# pmod_debug.net
KiCad netlist of a schematic drawn in EAGLE
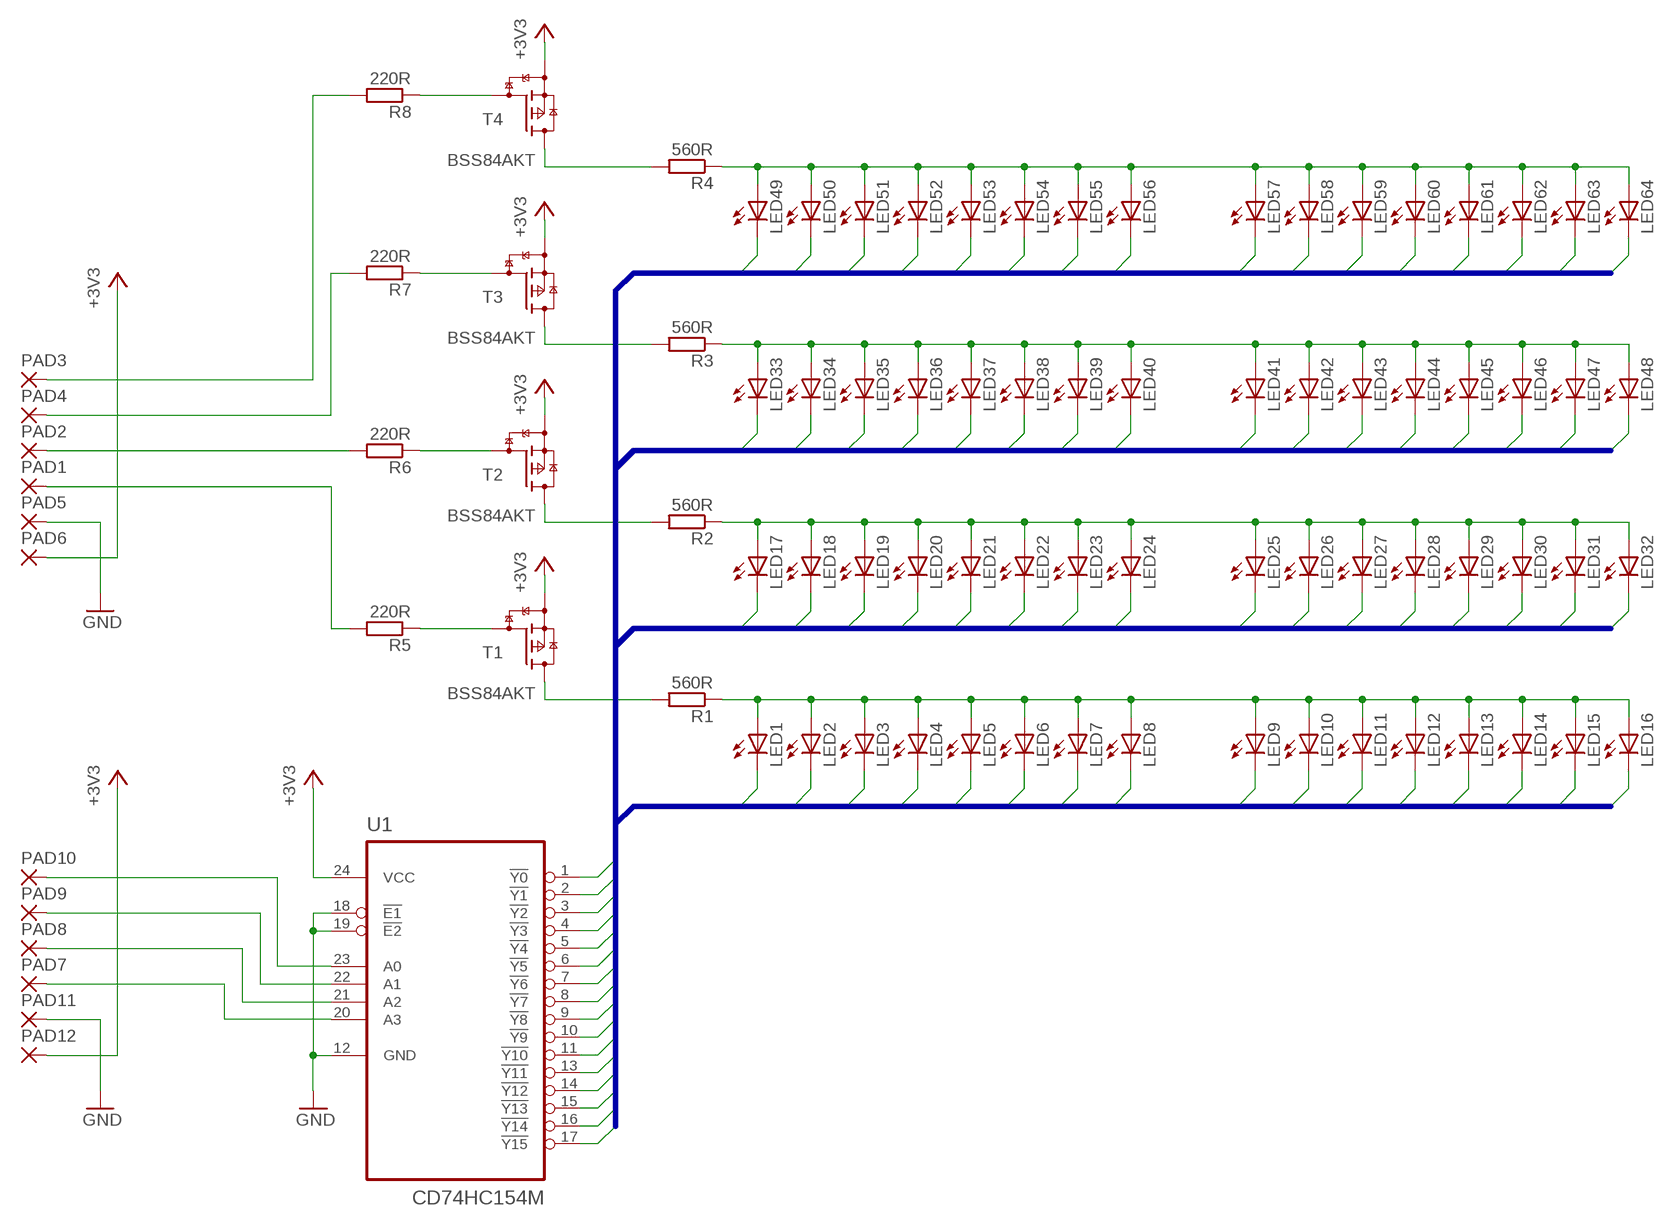
[diagram p0: schematic, sheet 1]

(export (version "E")
  (design (tool "Eeschema 10.0.6"))
  (components
    (comp (ref "LED1")
      (value "LEDCHIP-LED0603")
      (footprint "eagle-import:CHIP-LED0603")
      (libsource (lib "eagle-import") (part "LEDCHIP-LED0603"))
    )
    (comp (ref "LED2")
      (value "LEDCHIP-LED0603")
      (footprint "eagle-import:CHIP-LED0603")
      (libsource (lib "eagle-import") (part "LEDCHIP-LED0603"))
    )
    (comp (ref "LED3")
      (value "LEDCHIP-LED0603")
      (footprint "eagle-import:CHIP-LED0603")
      (libsource (lib "eagle-import") (part "LEDCHIP-LED0603"))
    )
    (comp (ref "LED4")
      (value "LEDCHIP-LED0603")
      (footprint "eagle-import:CHIP-LED0603")
      (libsource (lib "eagle-import") (part "LEDCHIP-LED0603"))
    )
    (comp (ref "LED5")
      (value "LEDCHIP-LED0603")
      (footprint "eagle-import:CHIP-LED0603")
      (libsource (lib "eagle-import") (part "LEDCHIP-LED0603"))
    )
    (comp (ref "LED6")
      (value "LEDCHIP-LED0603")
      (footprint "eagle-import:CHIP-LED0603")
      (libsource (lib "eagle-import") (part "LEDCHIP-LED0603"))
    )
    (comp (ref "LED7")
      (value "LEDCHIP-LED0603")
      (footprint "eagle-import:CHIP-LED0603")
      (libsource (lib "eagle-import") (part "LEDCHIP-LED0603"))
    )
    (comp (ref "LED8")
      (value "LEDCHIP-LED0603")
      (footprint "eagle-import:CHIP-LED0603")
      (libsource (lib "eagle-import") (part "LEDCHIP-LED0603"))
    )
    (comp (ref "LED9")
      (value "LEDCHIP-LED0603")
      (footprint "eagle-import:CHIP-LED0603")
      (libsource (lib "eagle-import") (part "LEDCHIP-LED0603"))
    )
    (comp (ref "LED10")
      (value "LEDCHIP-LED0603")
      (footprint "eagle-import:CHIP-LED0603")
      (libsource (lib "eagle-import") (part "LEDCHIP-LED0603"))
    )
    (comp (ref "LED11")
      (value "LEDCHIP-LED0603")
      (footprint "eagle-import:CHIP-LED0603")
      (libsource (lib "eagle-import") (part "LEDCHIP-LED0603"))
    )
    (comp (ref "LED12")
      (value "LEDCHIP-LED0603")
      (footprint "eagle-import:CHIP-LED0603")
      (libsource (lib "eagle-import") (part "LEDCHIP-LED0603"))
    )
    (comp (ref "LED13")
      (value "LEDCHIP-LED0603")
      (footprint "eagle-import:CHIP-LED0603")
      (libsource (lib "eagle-import") (part "LEDCHIP-LED0603"))
    )
    (comp (ref "LED14")
      (value "LEDCHIP-LED0603")
      (footprint "eagle-import:CHIP-LED0603")
      (libsource (lib "eagle-import") (part "LEDCHIP-LED0603"))
    )
    (comp (ref "LED15")
      (value "LEDCHIP-LED0603")
      (footprint "eagle-import:CHIP-LED0603")
      (libsource (lib "eagle-import") (part "LEDCHIP-LED0603"))
    )
    (comp (ref "LED16")
      (value "LEDCHIP-LED0603")
      (footprint "eagle-import:CHIP-LED0603")
      (libsource (lib "eagle-import") (part "LEDCHIP-LED0603"))
    )
    (comp (ref "LED17")
      (value "LEDCHIP-LED0603")
      (footprint "eagle-import:CHIP-LED0603")
      (libsource (lib "eagle-import") (part "LEDCHIP-LED0603"))
    )
    (comp (ref "LED18")
      (value "LEDCHIP-LED0603")
      (footprint "eagle-import:CHIP-LED0603")
      (libsource (lib "eagle-import") (part "LEDCHIP-LED0603"))
    )
    (comp (ref "LED19")
      (value "LEDCHIP-LED0603")
      (footprint "eagle-import:CHIP-LED0603")
      (libsource (lib "eagle-import") (part "LEDCHIP-LED0603"))
    )
    (comp (ref "LED20")
      (value "LEDCHIP-LED0603")
      (footprint "eagle-import:CHIP-LED0603")
      (libsource (lib "eagle-import") (part "LEDCHIP-LED0603"))
    )
    (comp (ref "LED21")
      (value "LEDCHIP-LED0603")
      (footprint "eagle-import:CHIP-LED0603")
      (libsource (lib "eagle-import") (part "LEDCHIP-LED0603"))
    )
    (comp (ref "LED22")
      (value "LEDCHIP-LED0603")
      (footprint "eagle-import:CHIP-LED0603")
      (libsource (lib "eagle-import") (part "LEDCHIP-LED0603"))
    )
    (comp (ref "LED23")
      (value "LEDCHIP-LED0603")
      (footprint "eagle-import:CHIP-LED0603")
      (libsource (lib "eagle-import") (part "LEDCHIP-LED0603"))
    )
    (comp (ref "LED24")
      (value "LEDCHIP-LED0603")
      (footprint "eagle-import:CHIP-LED0603")
      (libsource (lib "eagle-import") (part "LEDCHIP-LED0603"))
    )
    (comp (ref "LED25")
      (value "LEDCHIP-LED0603")
      (footprint "eagle-import:CHIP-LED0603")
      (libsource (lib "eagle-import") (part "LEDCHIP-LED0603"))
    )
    (comp (ref "LED26")
      (value "LEDCHIP-LED0603")
      (footprint "eagle-import:CHIP-LED0603")
      (libsource (lib "eagle-import") (part "LEDCHIP-LED0603"))
    )
    (comp (ref "LED27")
      (value "LEDCHIP-LED0603")
      (footprint "eagle-import:CHIP-LED0603")
      (libsource (lib "eagle-import") (part "LEDCHIP-LED0603"))
    )
    (comp (ref "LED28")
      (value "LEDCHIP-LED0603")
      (footprint "eagle-import:CHIP-LED0603")
      (libsource (lib "eagle-import") (part "LEDCHIP-LED0603"))
    )
    (comp (ref "LED29")
      (value "LEDCHIP-LED0603")
      (footprint "eagle-import:CHIP-LED0603")
      (libsource (lib "eagle-import") (part "LEDCHIP-LED0603"))
    )
    (comp (ref "LED30")
      (value "LEDCHIP-LED0603")
      (footprint "eagle-import:CHIP-LED0603")
      (libsource (lib "eagle-import") (part "LEDCHIP-LED0603"))
    )
    (comp (ref "LED31")
      (value "LEDCHIP-LED0603")
      (footprint "eagle-import:CHIP-LED0603")
      (libsource (lib "eagle-import") (part "LEDCHIP-LED0603"))
    )
    (comp (ref "LED32")
      (value "LEDCHIP-LED0603")
      (footprint "eagle-import:CHIP-LED0603")
      (libsource (lib "eagle-import") (part "LEDCHIP-LED0603"))
    )
    (comp (ref "LED33")
      (value "LEDCHIP-LED0603")
      (footprint "eagle-import:CHIP-LED0603")
      (libsource (lib "eagle-import") (part "LEDCHIP-LED0603"))
    )
    (comp (ref "LED34")
      (value "LEDCHIP-LED0603")
      (footprint "eagle-import:CHIP-LED0603")
      (libsource (lib "eagle-import") (part "LEDCHIP-LED0603"))
    )
    (comp (ref "LED35")
      (value "LEDCHIP-LED0603")
      (footprint "eagle-import:CHIP-LED0603")
      (libsource (lib "eagle-import") (part "LEDCHIP-LED0603"))
    )
    (comp (ref "LED36")
      (value "LEDCHIP-LED0603")
      (footprint "eagle-import:CHIP-LED0603")
      (libsource (lib "eagle-import") (part "LEDCHIP-LED0603"))
    )
    (comp (ref "LED37")
      (value "LEDCHIP-LED0603")
      (footprint "eagle-import:CHIP-LED0603")
      (libsource (lib "eagle-import") (part "LEDCHIP-LED0603"))
    )
    (comp (ref "LED38")
      (value "LEDCHIP-LED0603")
      (footprint "eagle-import:CHIP-LED0603")
      (libsource (lib "eagle-import") (part "LEDCHIP-LED0603"))
    )
    (comp (ref "LED39")
      (value "LEDCHIP-LED0603")
      (footprint "eagle-import:CHIP-LED0603")
      (libsource (lib "eagle-import") (part "LEDCHIP-LED0603"))
    )
    (comp (ref "LED40")
      (value "LEDCHIP-LED0603")
      (footprint "eagle-import:CHIP-LED0603")
      (libsource (lib "eagle-import") (part "LEDCHIP-LED0603"))
    )
    (comp (ref "LED41")
      (value "LEDCHIP-LED0603")
      (footprint "eagle-import:CHIP-LED0603")
      (libsource (lib "eagle-import") (part "LEDCHIP-LED0603"))
    )
    (comp (ref "LED42")
      (value "LEDCHIP-LED0603")
      (footprint "eagle-import:CHIP-LED0603")
      (libsource (lib "eagle-import") (part "LEDCHIP-LED0603"))
    )
    (comp (ref "LED43")
      (value "LEDCHIP-LED0603")
      (footprint "eagle-import:CHIP-LED0603")
      (libsource (lib "eagle-import") (part "LEDCHIP-LED0603"))
    )
    (comp (ref "LED44")
      (value "LEDCHIP-LED0603")
      (footprint "eagle-import:CHIP-LED0603")
      (libsource (lib "eagle-import") (part "LEDCHIP-LED0603"))
    )
    (comp (ref "LED45")
      (value "LEDCHIP-LED0603")
      (footprint "eagle-import:CHIP-LED0603")
      (libsource (lib "eagle-import") (part "LEDCHIP-LED0603"))
    )
    (comp (ref "LED46")
      (value "LEDCHIP-LED0603")
      (footprint "eagle-import:CHIP-LED0603")
      (libsource (lib "eagle-import") (part "LEDCHIP-LED0603"))
    )
    (comp (ref "LED47")
      (value "LEDCHIP-LED0603")
      (footprint "eagle-import:CHIP-LED0603")
      (libsource (lib "eagle-import") (part "LEDCHIP-LED0603"))
    )
    (comp (ref "LED48")
      (value "LEDCHIP-LED0603")
      (footprint "eagle-import:CHIP-LED0603")
      (libsource (lib "eagle-import") (part "LEDCHIP-LED0603"))
    )
    (comp (ref "LED49")
      (value "LEDCHIP-LED0603")
      (footprint "eagle-import:CHIP-LED0603")
      (libsource (lib "eagle-import") (part "LEDCHIP-LED0603"))
    )
    (comp (ref "LED50")
      (value "LEDCHIP-LED0603")
      (footprint "eagle-import:CHIP-LED0603")
      (libsource (lib "eagle-import") (part "LEDCHIP-LED0603"))
    )
    (comp (ref "LED51")
      (value "LEDCHIP-LED0603")
      (footprint "eagle-import:CHIP-LED0603")
      (libsource (lib "eagle-import") (part "LEDCHIP-LED0603"))
    )
    (comp (ref "LED52")
      (value "LEDCHIP-LED0603")
      (footprint "eagle-import:CHIP-LED0603")
      (libsource (lib "eagle-import") (part "LEDCHIP-LED0603"))
    )
    (comp (ref "LED53")
      (value "LEDCHIP-LED0603")
      (footprint "eagle-import:CHIP-LED0603")
      (libsource (lib "eagle-import") (part "LEDCHIP-LED0603"))
    )
    (comp (ref "LED54")
      (value "LEDCHIP-LED0603")
      (footprint "eagle-import:CHIP-LED0603")
      (libsource (lib "eagle-import") (part "LEDCHIP-LED0603"))
    )
    (comp (ref "LED55")
      (value "LEDCHIP-LED0603")
      (footprint "eagle-import:CHIP-LED0603")
      (libsource (lib "eagle-import") (part "LEDCHIP-LED0603"))
    )
    (comp (ref "LED56")
      (value "LEDCHIP-LED0603")
      (footprint "eagle-import:CHIP-LED0603")
      (libsource (lib "eagle-import") (part "LEDCHIP-LED0603"))
    )
    (comp (ref "LED57")
      (value "LEDCHIP-LED0603")
      (footprint "eagle-import:CHIP-LED0603")
      (libsource (lib "eagle-import") (part "LEDCHIP-LED0603"))
    )
    (comp (ref "LED58")
      (value "LEDCHIP-LED0603")
      (footprint "eagle-import:CHIP-LED0603")
      (libsource (lib "eagle-import") (part "LEDCHIP-LED0603"))
    )
    (comp (ref "LED59")
      (value "LEDCHIP-LED0603")
      (footprint "eagle-import:CHIP-LED0603")
      (libsource (lib "eagle-import") (part "LEDCHIP-LED0603"))
    )
    (comp (ref "LED60")
      (value "LEDCHIP-LED0603")
      (footprint "eagle-import:CHIP-LED0603")
      (libsource (lib "eagle-import") (part "LEDCHIP-LED0603"))
    )
    (comp (ref "LED61")
      (value "LEDCHIP-LED0603")
      (footprint "eagle-import:CHIP-LED0603")
      (libsource (lib "eagle-import") (part "LEDCHIP-LED0603"))
    )
    (comp (ref "LED62")
      (value "LEDCHIP-LED0603")
      (footprint "eagle-import:CHIP-LED0603")
      (libsource (lib "eagle-import") (part "LEDCHIP-LED0603"))
    )
    (comp (ref "LED63")
      (value "LEDCHIP-LED0603")
      (footprint "eagle-import:CHIP-LED0603")
      (libsource (lib "eagle-import") (part "LEDCHIP-LED0603"))
    )
    (comp (ref "LED64")
      (value "LEDCHIP-LED0603")
      (footprint "eagle-import:CHIP-LED0603")
      (libsource (lib "eagle-import") (part "LEDCHIP-LED0603"))
    )
    (comp (ref "PAD1")
      (value "SMD2HR")
      (footprint "eagle-import:SMD1.27-3.175HR")
      (libsource (lib "eagle-import") (part "SMD2HR"))
    )
    (comp (ref "PAD2")
      (value "SMD2HR")
      (footprint "eagle-import:SMD1.27-3.175HR")
      (libsource (lib "eagle-import") (part "SMD2HR"))
    )
    (comp (ref "PAD3")
      (value "SMD2HR")
      (footprint "eagle-import:SMD1.27-3.175HR")
      (libsource (lib "eagle-import") (part "SMD2HR"))
    )
    (comp (ref "PAD4")
      (value "SMD2HR")
      (footprint "eagle-import:SMD1.27-3.175HR")
      (libsource (lib "eagle-import") (part "SMD2HR"))
    )
    (comp (ref "PAD5")
      (value "SMD2HR")
      (footprint "eagle-import:SMD1.27-3.175HR")
      (libsource (lib "eagle-import") (part "SMD2HR"))
    )
    (comp (ref "PAD6")
      (value "SMD2HR")
      (footprint "eagle-import:SMD1.27-3.175HR")
      (libsource (lib "eagle-import") (part "SMD2HR"))
    )
    (comp (ref "PAD7")
      (value "SMD2HR")
      (footprint "eagle-import:SMD1.27-3.175HR")
      (libsource (lib "eagle-import") (part "SMD2HR"))
    )
    (comp (ref "PAD8")
      (value "SMD2HR")
      (footprint "eagle-import:SMD1.27-3.175HR")
      (libsource (lib "eagle-import") (part "SMD2HR"))
    )
    (comp (ref "PAD9")
      (value "SMD2HR")
      (footprint "eagle-import:SMD1.27-3.175HR")
      (libsource (lib "eagle-import") (part "SMD2HR"))
    )
    (comp (ref "PAD10")
      (value "SMD2HR")
      (footprint "eagle-import:SMD1.27-3.175HR")
      (libsource (lib "eagle-import") (part "SMD2HR"))
    )
    (comp (ref "PAD11")
      (value "SMD2HR")
      (footprint "eagle-import:SMD1.27-3.175HR")
      (libsource (lib "eagle-import") (part "SMD2HR"))
    )
    (comp (ref "PAD12")
      (value "SMD2HR")
      (footprint "eagle-import:SMD1.27-3.175HR")
      (libsource (lib "eagle-import") (part "SMD2HR"))
    )
    (comp (ref "R1")
      (value "560R")
      (footprint "eagle-import:R0402")
      (libsource (lib "eagle-import") (part "R-EU_R0402"))
    )
    (comp (ref "R2")
      (value "560R")
      (footprint "eagle-import:R0402")
      (libsource (lib "eagle-import") (part "R-EU_R0402"))
    )
    (comp (ref "R3")
      (value "560R")
      (footprint "eagle-import:R0402")
      (libsource (lib "eagle-import") (part "R-EU_R0402"))
    )
    (comp (ref "R4")
      (value "560R")
      (footprint "eagle-import:R0402")
      (libsource (lib "eagle-import") (part "R-EU_R0402"))
    )
    (comp (ref "R5")
      (value "220R")
      (footprint "eagle-import:R0402")
      (libsource (lib "eagle-import") (part "R-EU_R0402"))
    )
    (comp (ref "R6")
      (value "220R")
      (footprint "eagle-import:R0402")
      (libsource (lib "eagle-import") (part "R-EU_R0402"))
    )
    (comp (ref "R7")
      (value "220R")
      (footprint "eagle-import:R0402")
      (libsource (lib "eagle-import") (part "R-EU_R0402"))
    )
    (comp (ref "R8")
      (value "220R")
      (footprint "eagle-import:R0402")
      (libsource (lib "eagle-import") (part "R-EU_R0402"))
    )
    (comp (ref "T1")
      (value "BSS84AKT")
      (footprint "eagle-import:SOT416")
      (libsource (lib "eagle-import") (part "BSS84AKT"))
    )
    (comp (ref "T2")
      (value "BSS84AKT")
      (footprint "eagle-import:SOT416")
      (libsource (lib "eagle-import") (part "BSS84AKT"))
    )
    (comp (ref "T3")
      (value "BSS84AKT")
      (footprint "eagle-import:SOT416")
      (libsource (lib "eagle-import") (part "BSS84AKT"))
    )
    (comp (ref "T4")
      (value "BSS84AKT")
      (footprint "eagle-import:SOT416")
      (libsource (lib "eagle-import") (part "BSS84AKT"))
    )
    (comp (ref "U1")
      (value "CD74HC154M")
      (footprint "eagle-import:SOIC127P1030X265-24N")
      (libsource (lib "eagle-import") (part "CD74HC154M"))
    )
  )
  (nets
    (net (code "1") (name "+3V3") (class "Default")
      (node (ref "PAD12") (pin "1") (pinfunction "P_1") (pintype "passive"))
      (node (ref "PAD6") (pin "1") (pinfunction "P_1") (pintype "passive"))
      (node (ref "T1") (pin "2") (pinfunction "S_2") (pintype "passive"))
      (node (ref "T2") (pin "2") (pinfunction "S_2") (pintype "passive"))
      (node (ref "T3") (pin "2") (pinfunction "S_2") (pintype "passive"))
      (node (ref "T4") (pin "2") (pinfunction "S_2") (pintype "passive"))
      (node (ref "U1") (pin "24") (pinfunction "VCC_24") (pintype "power_in"))
    )
    (net (code "2") (name "/C0") (class "Default")
      (node (ref "LED1") (pin "C") (pinfunction "C_C") (pintype "passive"))
      (node (ref "LED17") (pin "C") (pinfunction "C_C") (pintype "passive"))
      (node (ref "LED33") (pin "C") (pinfunction "C_C") (pintype "passive"))
      (node (ref "LED49") (pin "C") (pinfunction "C_C") (pintype "passive"))
      (node (ref "U1") (pin "1") (pinfunction "~{Y0}_1") (pintype "output"))
    )
    (net (code "3") (name "/C1") (class "Default")
      (node (ref "LED18") (pin "C") (pinfunction "C_C") (pintype "passive"))
      (node (ref "LED2") (pin "C") (pinfunction "C_C") (pintype "passive"))
      (node (ref "LED34") (pin "C") (pinfunction "C_C") (pintype "passive"))
      (node (ref "LED50") (pin "C") (pinfunction "C_C") (pintype "passive"))
      (node (ref "U1") (pin "2") (pinfunction "~{Y1}_2") (pintype "output"))
    )
    (net (code "4") (name "/C2") (class "Default")
      (node (ref "LED19") (pin "C") (pinfunction "C_C") (pintype "passive"))
      (node (ref "LED3") (pin "C") (pinfunction "C_C") (pintype "passive"))
      (node (ref "LED35") (pin "C") (pinfunction "C_C") (pintype "passive"))
      (node (ref "LED51") (pin "C") (pinfunction "C_C") (pintype "passive"))
      (node (ref "U1") (pin "3") (pinfunction "~{Y2}_3") (pintype "output"))
    )
    (net (code "5") (name "/C3") (class "Default")
      (node (ref "LED20") (pin "C") (pinfunction "C_C") (pintype "passive"))
      (node (ref "LED36") (pin "C") (pinfunction "C_C") (pintype "passive"))
      (node (ref "LED4") (pin "C") (pinfunction "C_C") (pintype "passive"))
      (node (ref "LED52") (pin "C") (pinfunction "C_C") (pintype "passive"))
      (node (ref "U1") (pin "4") (pinfunction "~{Y3}_4") (pintype "output"))
    )
    (net (code "6") (name "/C4") (class "Default")
      (node (ref "LED21") (pin "C") (pinfunction "C_C") (pintype "passive"))
      (node (ref "LED37") (pin "C") (pinfunction "C_C") (pintype "passive"))
      (node (ref "LED5") (pin "C") (pinfunction "C_C") (pintype "passive"))
      (node (ref "LED53") (pin "C") (pinfunction "C_C") (pintype "passive"))
      (node (ref "U1") (pin "5") (pinfunction "~{Y4}_5") (pintype "output"))
    )
    (net (code "7") (name "/C5") (class "Default")
      (node (ref "LED22") (pin "C") (pinfunction "C_C") (pintype "passive"))
      (node (ref "LED38") (pin "C") (pinfunction "C_C") (pintype "passive"))
      (node (ref "LED54") (pin "C") (pinfunction "C_C") (pintype "passive"))
      (node (ref "LED6") (pin "C") (pinfunction "C_C") (pintype "passive"))
      (node (ref "U1") (pin "6") (pinfunction "~{Y5}_6") (pintype "output"))
    )
    (net (code "8") (name "/C6") (class "Default")
      (node (ref "LED23") (pin "C") (pinfunction "C_C") (pintype "passive"))
      (node (ref "LED39") (pin "C") (pinfunction "C_C") (pintype "passive"))
      (node (ref "LED55") (pin "C") (pinfunction "C_C") (pintype "passive"))
      (node (ref "LED7") (pin "C") (pinfunction "C_C") (pintype "passive"))
      (node (ref "U1") (pin "7") (pinfunction "~{Y6}_7") (pintype "output"))
    )
    (net (code "9") (name "/C7") (class "Default")
      (node (ref "LED24") (pin "C") (pinfunction "C_C") (pintype "passive"))
      (node (ref "LED40") (pin "C") (pinfunction "C_C") (pintype "passive"))
      (node (ref "LED56") (pin "C") (pinfunction "C_C") (pintype "passive"))
      (node (ref "LED8") (pin "C") (pinfunction "C_C") (pintype "passive"))
      (node (ref "U1") (pin "8") (pinfunction "~{Y7}_8") (pintype "output"))
    )
    (net (code "10") (name "/C8") (class "Default")
      (node (ref "LED25") (pin "C") (pinfunction "C_C") (pintype "passive"))
      (node (ref "LED41") (pin "C") (pinfunction "C_C") (pintype "passive"))
      (node (ref "LED57") (pin "C") (pinfunction "C_C") (pintype "passive"))
      (node (ref "LED9") (pin "C") (pinfunction "C_C") (pintype "passive"))
      (node (ref "U1") (pin "9") (pinfunction "~{Y8}_9") (pintype "output"))
    )
    (net (code "11") (name "/C9") (class "Default")
      (node (ref "LED10") (pin "C") (pinfunction "C_C") (pintype "passive"))
      (node (ref "LED26") (pin "C") (pinfunction "C_C") (pintype "passive"))
      (node (ref "LED42") (pin "C") (pinfunction "C_C") (pintype "passive"))
      (node (ref "LED58") (pin "C") (pinfunction "C_C") (pintype "passive"))
      (node (ref "U1") (pin "10") (pinfunction "~{Y9}_10") (pintype "output"))
    )
    (net (code "12") (name "/C10") (class "Default")
      (node (ref "LED11") (pin "C") (pinfunction "C_C") (pintype "passive"))
      (node (ref "LED27") (pin "C") (pinfunction "C_C") (pintype "passive"))
      (node (ref "LED43") (pin "C") (pinfunction "C_C") (pintype "passive"))
      (node (ref "LED59") (pin "C") (pinfunction "C_C") (pintype "passive"))
      (node (ref "U1") (pin "11") (pinfunction "~{Y10}_11") (pintype "output"))
    )
    (net (code "13") (name "/C11") (class "Default")
      (node (ref "LED12") (pin "C") (pinfunction "C_C") (pintype "passive"))
      (node (ref "LED28") (pin "C") (pinfunction "C_C") (pintype "passive"))
      (node (ref "LED44") (pin "C") (pinfunction "C_C") (pintype "passive"))
      (node (ref "LED60") (pin "C") (pinfunction "C_C") (pintype "passive"))
      (node (ref "U1") (pin "13") (pinfunction "~{Y11}_13") (pintype "output"))
    )
    (net (code "14") (name "/C12") (class "Default")
      (node (ref "LED13") (pin "C") (pinfunction "C_C") (pintype "passive"))
      (node (ref "LED29") (pin "C") (pinfunction "C_C") (pintype "passive"))
      (node (ref "LED45") (pin "C") (pinfunction "C_C") (pintype "passive"))
      (node (ref "LED61") (pin "C") (pinfunction "C_C") (pintype "passive"))
      (node (ref "U1") (pin "14") (pinfunction "~{Y12}_14") (pintype "output"))
    )
    (net (code "15") (name "/C13") (class "Default")
      (node (ref "LED14") (pin "C") (pinfunction "C_C") (pintype "passive"))
      (node (ref "LED30") (pin "C") (pinfunction "C_C") (pintype "passive"))
      (node (ref "LED46") (pin "C") (pinfunction "C_C") (pintype "passive"))
      (node (ref "LED62") (pin "C") (pinfunction "C_C") (pintype "passive"))
      (node (ref "U1") (pin "15") (pinfunction "~{Y13}_15") (pintype "output"))
    )
    (net (code "16") (name "/C14") (class "Default")
      (node (ref "LED15") (pin "C") (pinfunction "C_C") (pintype "passive"))
      (node (ref "LED31") (pin "C") (pinfunction "C_C") (pintype "passive"))
      (node (ref "LED47") (pin "C") (pinfunction "C_C") (pintype "passive"))
      (node (ref "LED63") (pin "C") (pinfunction "C_C") (pintype "passive"))
      (node (ref "U1") (pin "16") (pinfunction "~{Y14}_16") (pintype "output"))
    )
    (net (code "17") (name "/C15") (class "Default")
      (node (ref "LED16") (pin "C") (pinfunction "C_C") (pintype "passive"))
      (node (ref "LED32") (pin "C") (pinfunction "C_C") (pintype "passive"))
      (node (ref "LED48") (pin "C") (pinfunction "C_C") (pintype "passive"))
      (node (ref "LED64") (pin "C") (pinfunction "C_C") (pintype "passive"))
      (node (ref "U1") (pin "17") (pinfunction "~{Y15}_17") (pintype "output"))
    )
    (net (code "18") (name "GND") (class "Default")
      (node (ref "PAD11") (pin "1") (pinfunction "P_1") (pintype "passive"))
      (node (ref "PAD5") (pin "1") (pinfunction "P_1") (pintype "passive"))
      (node (ref "U1") (pin "12") (pinfunction "GND_12") (pintype "passive"))
      (node (ref "U1") (pin "18") (pinfunction "~{E1}_18") (pintype "input"))
      (node (ref "U1") (pin "19") (pinfunction "~{E2}_19") (pintype "input"))
    )
    (net (code "19") (name "Net-(LED1-PadA)") (class "Default")
      (node (ref "LED1") (pin "A") (pinfunction "A_A") (pintype "passive"))
      (node (ref "LED10") (pin "A") (pinfunction "A_A") (pintype "passive"))
      (node (ref "LED11") (pin "A") (pinfunction "A_A") (pintype "passive"))
      (node (ref "LED12") (pin "A") (pinfunction "A_A") (pintype "passive"))
      (node (ref "LED13") (pin "A") (pinfunction "A_A") (pintype "passive"))
      (node (ref "LED14") (pin "A") (pinfunction "A_A") (pintype "passive"))
      (node (ref "LED15") (pin "A") (pinfunction "A_A") (pintype "passive"))
      (node (ref "LED16") (pin "A") (pinfunction "A_A") (pintype "passive"))
      (node (ref "LED2") (pin "A") (pinfunction "A_A") (pintype "passive"))
      (node (ref "LED3") (pin "A") (pinfunction "A_A") (pintype "passive"))
      (node (ref "LED4") (pin "A") (pinfunction "A_A") (pintype "passive"))
      (node (ref "LED5") (pin "A") (pinfunction "A_A") (pintype "passive"))
      (node (ref "LED6") (pin "A") (pinfunction "A_A") (pintype "passive"))
      (node (ref "LED7") (pin "A") (pinfunction "A_A") (pintype "passive"))
      (node (ref "LED8") (pin "A") (pinfunction "A_A") (pintype "passive"))
      (node (ref "LED9") (pin "A") (pinfunction "A_A") (pintype "passive"))
      (node (ref "R1") (pin "1") (pinfunction "1_1") (pintype "passive"))
    )
    (net (code "20") (name "Net-(LED17-PadA)") (class "Default")
      (node (ref "LED17") (pin "A") (pinfunction "A_A") (pintype "passive"))
      (node (ref "LED18") (pin "A") (pinfunction "A_A") (pintype "passive"))
      (node (ref "LED19") (pin "A") (pinfunction "A_A") (pintype "passive"))
      (node (ref "LED20") (pin "A") (pinfunction "A_A") (pintype "passive"))
      (node (ref "LED21") (pin "A") (pinfunction "A_A") (pintype "passive"))
      (node (ref "LED22") (pin "A") (pinfunction "A_A") (pintype "passive"))
      (node (ref "LED23") (pin "A") (pinfunction "A_A") (pintype "passive"))
      (node (ref "LED24") (pin "A") (pinfunction "A_A") (pintype "passive"))
      (node (ref "LED25") (pin "A") (pinfunction "A_A") (pintype "passive"))
      (node (ref "LED26") (pin "A") (pinfunction "A_A") (pintype "passive"))
      (node (ref "LED27") (pin "A") (pinfunction "A_A") (pintype "passive"))
      (node (ref "LED28") (pin "A") (pinfunction "A_A") (pintype "passive"))
      (node (ref "LED29") (pin "A") (pinfunction "A_A") (pintype "passive"))
      (node (ref "LED30") (pin "A") (pinfunction "A_A") (pintype "passive"))
      (node (ref "LED31") (pin "A") (pinfunction "A_A") (pintype "passive"))
      (node (ref "LED32") (pin "A") (pinfunction "A_A") (pintype "passive"))
      (node (ref "R2") (pin "1") (pinfunction "1_1") (pintype "passive"))
    )
    (net (code "21") (name "Net-(LED33-PadA)") (class "Default")
      (node (ref "LED33") (pin "A") (pinfunction "A_A") (pintype "passive"))
      (node (ref "LED34") (pin "A") (pinfunction "A_A") (pintype "passive"))
      (node (ref "LED35") (pin "A") (pinfunction "A_A") (pintype "passive"))
      (node (ref "LED36") (pin "A") (pinfunction "A_A") (pintype "passive"))
      (node (ref "LED37") (pin "A") (pinfunction "A_A") (pintype "passive"))
      (node (ref "LED38") (pin "A") (pinfunction "A_A") (pintype "passive"))
      (node (ref "LED39") (pin "A") (pinfunction "A_A") (pintype "passive"))
      (node (ref "LED40") (pin "A") (pinfunction "A_A") (pintype "passive"))
      (node (ref "LED41") (pin "A") (pinfunction "A_A") (pintype "passive"))
      (node (ref "LED42") (pin "A") (pinfunction "A_A") (pintype "passive"))
      (node (ref "LED43") (pin "A") (pinfunction "A_A") (pintype "passive"))
      (node (ref "LED44") (pin "A") (pinfunction "A_A") (pintype "passive"))
      (node (ref "LED45") (pin "A") (pinfunction "A_A") (pintype "passive"))
      (node (ref "LED46") (pin "A") (pinfunction "A_A") (pintype "passive"))
      (node (ref "LED47") (pin "A") (pinfunction "A_A") (pintype "passive"))
      (node (ref "LED48") (pin "A") (pinfunction "A_A") (pintype "passive"))
      (node (ref "R3") (pin "1") (pinfunction "1_1") (pintype "passive"))
    )
    (net (code "22") (name "Net-(LED49-PadA)") (class "Default")
      (node (ref "LED49") (pin "A") (pinfunction "A_A") (pintype "passive"))
      (node (ref "LED50") (pin "A") (pinfunction "A_A") (pintype "passive"))
      (node (ref "LED51") (pin "A") (pinfunction "A_A") (pintype "passive"))
      (node (ref "LED52") (pin "A") (pinfunction "A_A") (pintype "passive"))
      (node (ref "LED53") (pin "A") (pinfunction "A_A") (pintype "passive"))
      (node (ref "LED54") (pin "A") (pinfunction "A_A") (pintype "passive"))
      (node (ref "LED55") (pin "A") (pinfunction "A_A") (pintype "passive"))
      (node (ref "LED56") (pin "A") (pinfunction "A_A") (pintype "passive"))
      (node (ref "LED57") (pin "A") (pinfunction "A_A") (pintype "passive"))
      (node (ref "LED58") (pin "A") (pinfunction "A_A") (pintype "passive"))
      (node (ref "LED59") (pin "A") (pinfunction "A_A") (pintype "passive"))
      (node (ref "LED60") (pin "A") (pinfunction "A_A") (pintype "passive"))
      (node (ref "LED61") (pin "A") (pinfunction "A_A") (pintype "passive"))
      (node (ref "LED62") (pin "A") (pinfunction "A_A") (pintype "passive"))
      (node (ref "LED63") (pin "A") (pinfunction "A_A") (pintype "passive"))
      (node (ref "LED64") (pin "A") (pinfunction "A_A") (pintype "passive"))
      (node (ref "R4") (pin "1") (pinfunction "1_1") (pintype "passive"))
    )
    (net (code "23") (name "Net-(PAD1-P)") (class "Default")
      (node (ref "PAD1") (pin "1") (pinfunction "P_1") (pintype "passive"))
      (node (ref "R5") (pin "2") (pinfunction "2_2") (pintype "passive"))
    )
    (net (code "24") (name "Net-(PAD2-P)") (class "Default")
      (node (ref "PAD2") (pin "1") (pinfunction "P_1") (pintype "passive"))
      (node (ref "R6") (pin "2") (pinfunction "2_2") (pintype "passive"))
    )
    (net (code "25") (name "Net-(PAD3-P)") (class "Default")
      (node (ref "PAD3") (pin "1") (pinfunction "P_1") (pintype "passive"))
      (node (ref "R8") (pin "2") (pinfunction "2_2") (pintype "passive"))
    )
    (net (code "26") (name "Net-(PAD4-P)") (class "Default")
      (node (ref "PAD4") (pin "1") (pinfunction "P_1") (pintype "passive"))
      (node (ref "R7") (pin "2") (pinfunction "2_2") (pintype "passive"))
    )
    (net (code "27") (name "Net-(PAD7-P)") (class "Default")
      (node (ref "PAD7") (pin "1") (pinfunction "P_1") (pintype "passive"))
      (node (ref "U1") (pin "20") (pinfunction "A3_20") (pintype "input"))
    )
    (net (code "28") (name "Net-(PAD8-P)") (class "Default")
      (node (ref "PAD8") (pin "1") (pinfunction "P_1") (pintype "passive"))
      (node (ref "U1") (pin "21") (pinfunction "A2_21") (pintype "input"))
    )
    (net (code "29") (name "Net-(PAD9-P)") (class "Default")
      (node (ref "PAD9") (pin "1") (pinfunction "P_1") (pintype "passive"))
      (node (ref "U1") (pin "22") (pinfunction "A1_22") (pintype "input"))
    )
    (net (code "30") (name "Net-(PAD10-P)") (class "Default")
      (node (ref "PAD10") (pin "1") (pinfunction "P_1") (pintype "passive"))
      (node (ref "U1") (pin "23") (pinfunction "A0_23") (pintype "input"))
    )
    (net (code "31") (name "Net-(T1-D)") (class "Default")
      (node (ref "R1") (pin "2") (pinfunction "2_2") (pintype "passive"))
      (node (ref "T1") (pin "3") (pinfunction "D_3") (pintype "passive"))
    )
    (net (code "32") (name "Net-(T1-G)") (class "Default")
      (node (ref "R5") (pin "1") (pinfunction "1_1") (pintype "passive"))
      (node (ref "T1") (pin "1") (pinfunction "G_1") (pintype "passive"))
    )
    (net (code "33") (name "Net-(T2-D)") (class "Default")
      (node (ref "R2") (pin "2") (pinfunction "2_2") (pintype "passive"))
      (node (ref "T2") (pin "3") (pinfunction "D_3") (pintype "passive"))
    )
    (net (code "34") (name "Net-(T2-G)") (class "Default")
      (node (ref "R6") (pin "1") (pinfunction "1_1") (pintype "passive"))
      (node (ref "T2") (pin "1") (pinfunction "G_1") (pintype "passive"))
    )
    (net (code "35") (name "Net-(T3-D)") (class "Default")
      (node (ref "R3") (pin "2") (pinfunction "2_2") (pintype "passive"))
      (node (ref "T3") (pin "3") (pinfunction "D_3") (pintype "passive"))
    )
    (net (code "36") (name "Net-(T3-G)") (class "Default")
      (node (ref "R7") (pin "1") (pinfunction "1_1") (pintype "passive"))
      (node (ref "T3") (pin "1") (pinfunction "G_1") (pintype "passive"))
    )
    (net (code "37") (name "Net-(T4-D)") (class "Default")
      (node (ref "R4") (pin "2") (pinfunction "2_2") (pintype "passive"))
      (node (ref "T4") (pin "3") (pinfunction "D_3") (pintype "passive"))
    )
    (net (code "38") (name "Net-(T4-G)") (class "Default")
      (node (ref "R8") (pin "1") (pinfunction "1_1") (pintype "passive"))
      (node (ref "T4") (pin "1") (pinfunction "G_1") (pintype "passive"))
    )
  )
)
